# Main_Shield.net
KiCad netlist of a schematic drawn in Altium Designer
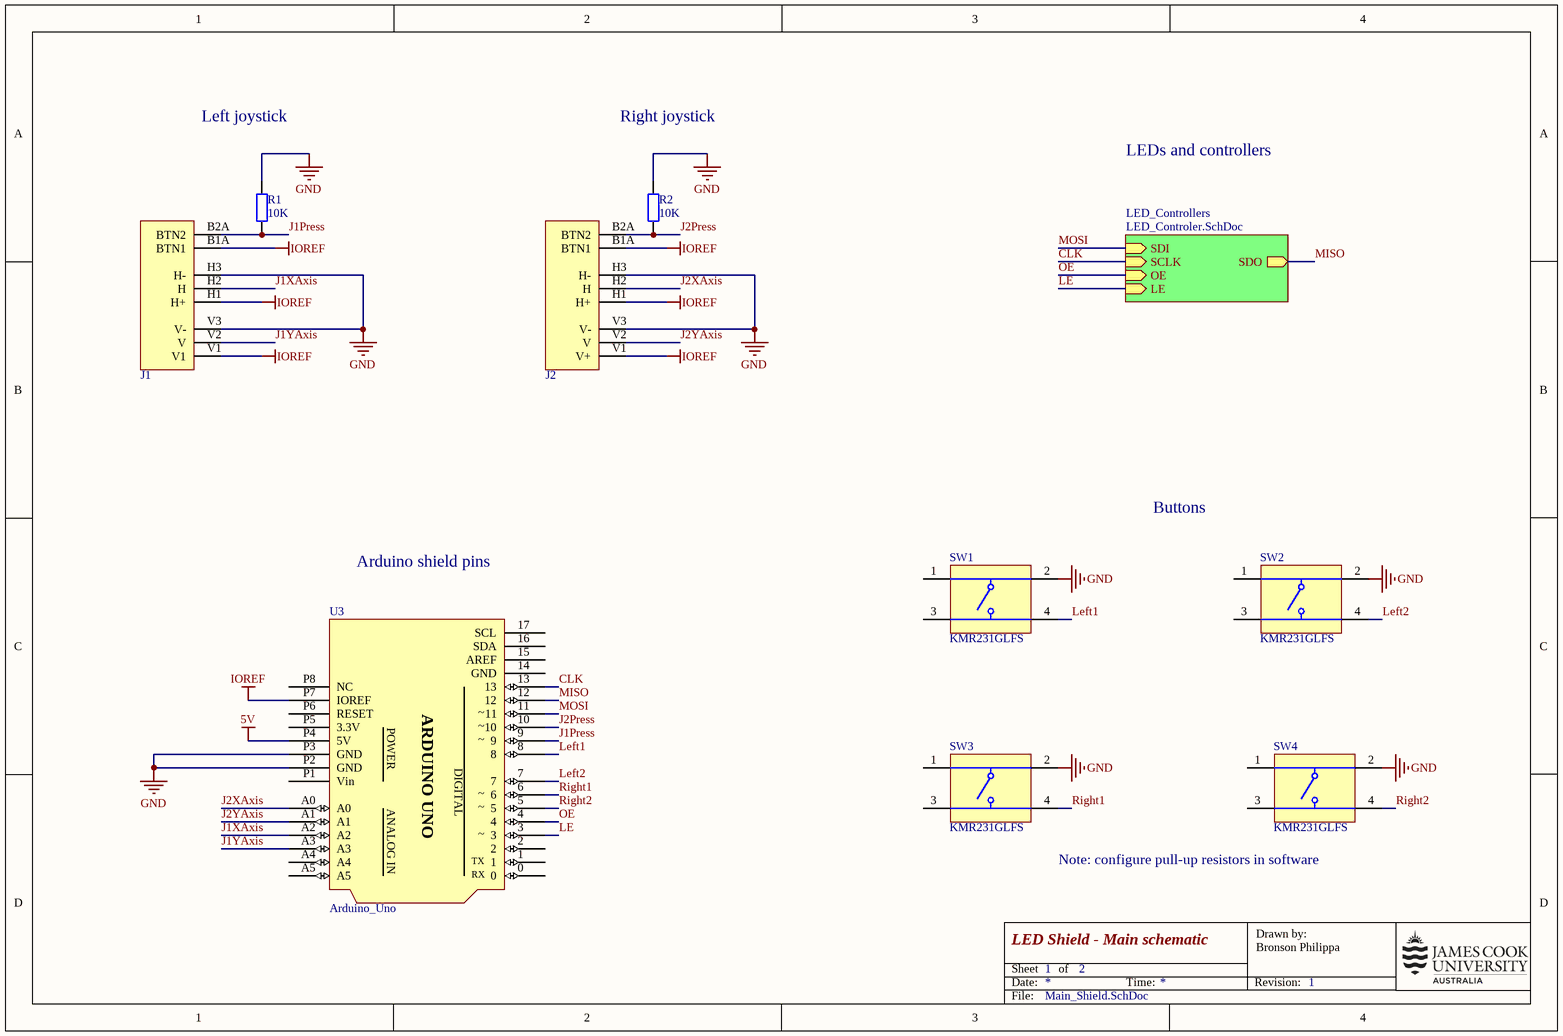
[diagram p0: Main_Shield.SchDoc]

(export (version "E")
  (design (tool "Eeschema 10.0.6"))
  (components
    (comp (ref "J1")
      (value "Joystick")
      (footprint "JOYSTICK")
      (description "Sparkfun Joystick COM-09032")
      (libsource (lib "JCULibrary") (part "Joystick"))
    )
    (comp (ref "J2")
      (value "Joystick")
      (footprint "JOYSTICK")
      (description "Sparkfun Joystick COM-09032")
      (libsource (lib "JCULibrary") (part "Joystick"))
    )
    (comp (ref "R1")
      (value "10K")
      (footprint "AXIAL-0.4")
      (description "Resistor")
      (fields (field (name "Comment") "Resistor Axial-0.4") (field (name "PUBLISHER") "Altium Limited"))
      (libsource (lib "JCULibrary") (part "Resistor Axial-0.4"))
    )
    (comp (ref "R2")
      (value "10K")
      (footprint "AXIAL-0.4")
      (description "Resistor")
      (fields (field (name "Comment") "Resistor Axial-0.4") (field (name "PUBLISHER") "Altium Limited"))
      (libsource (lib "JCULibrary") (part "Resistor Axial-0.4"))
    )
    (comp (ref "SW1")
      (value "KMR231GLFS")
      (footprint "CKCP-KMR231GLFS")
      (description "Switch Tactile, SPST, 50 mA, 32 V, -40 to 85 degC, 4-Pin SMD, RoHS, Tape and Reel")
      (fields (field (name "MANUFACTURER") "C&K Components"))
      (libsource (lib "Altium Content Vault") (part "SW-SPST-4_A"))
    )
    (comp (ref "SW2")
      (value "KMR231GLFS")
      (footprint "CKCP-KMR231GLFS")
      (description "Switch Tactile, SPST, 50 mA, 32 V, -40 to 85 degC, 4-Pin SMD, RoHS, Tape and Reel")
      (fields (field (name "MANUFACTURER") "C&K Components"))
      (libsource (lib "Altium Content Vault") (part "SW-SPST-4_A"))
    )
    (comp (ref "SW3")
      (value "KMR231GLFS")
      (footprint "CKCP-KMR231GLFS")
      (description "Switch Tactile, SPST, 50 mA, 32 V, -40 to 85 degC, 4-Pin SMD, RoHS, Tape and Reel")
      (fields (field (name "MANUFACTURER") "C&K Components"))
      (libsource (lib "Altium Content Vault") (part "SW-SPST-4_A"))
    )
    (comp (ref "SW4")
      (value "KMR231GLFS")
      (footprint "CKCP-KMR231GLFS")
      (description "Switch Tactile, SPST, 50 mA, 32 V, -40 to 85 degC, 4-Pin SMD, RoHS, Tape and Reel")
      (fields (field (name "MANUFACTURER") "C&K Components"))
      (libsource (lib "Altium Content Vault") (part "SW-SPST-4_A"))
    )
    (comp (ref "U3")
      (value "Arduino_Uno")
      (footprint "ArduinoUnoR3")
      (description "Template for building an Arduino shield")
      (libsource (lib "JCULibrary") (part "Arduino_Uno"))
    )
  )
  (nets
    (net (code "1") (name "/CLK") (class "Default")
      (node (ref "U3") (pin "13") (pinfunction "13_13") (pintype "bidirectional"))
    )
    (net (code "2") (name "/J1Press") (class "Default")
      (node (ref "J1") (pin "B2A") (pinfunction "BTN2_B2A") (pintype "passive"))
      (node (ref "R1") (pin "2") (pinfunction "2_2") (pintype "passive"))
      (node (ref "U3") (pin "9") (pinfunction "9_9") (pintype "bidirectional"))
    )
    (net (code "3") (name "/J1XAxis") (class "Default")
      (node (ref "J1") (pin "H2") (pinfunction "H_H2") (pintype "passive"))
      (node (ref "U3") (pin "A2") (pinfunction "A2_A2") (pintype "bidirectional"))
    )
    (net (code "4") (name "/J1YAxis") (class "Default")
      (node (ref "J1") (pin "V2") (pinfunction "V_V2") (pintype "passive"))
      (node (ref "U3") (pin "A3") (pinfunction "A3_A3") (pintype "bidirectional"))
    )
    (net (code "5") (name "/J2Press") (class "Default")
      (node (ref "J2") (pin "B2A") (pinfunction "BTN2_B2A") (pintype "passive"))
      (node (ref "R2") (pin "2") (pinfunction "2_2") (pintype "passive"))
      (node (ref "U3") (pin "10") (pinfunction "10_10") (pintype "bidirectional"))
    )
    (net (code "6") (name "/J2XAxis") (class "Default")
      (node (ref "J2") (pin "H2") (pinfunction "H_H2") (pintype "passive"))
      (node (ref "U3") (pin "A0") (pinfunction "A0_A0") (pintype "bidirectional"))
    )
    (net (code "7") (name "/J2YAxis") (class "Default")
      (node (ref "J2") (pin "V2") (pinfunction "V_V2") (pintype "passive"))
      (node (ref "U3") (pin "A1") (pinfunction "A1_A1") (pintype "bidirectional"))
    )
    (net (code "8") (name "/LE") (class "Default")
      (node (ref "U3") (pin "3") (pinfunction "3_3") (pintype "bidirectional"))
    )
    (net (code "9") (name "/Left1") (class "Default")
      (node (ref "SW1") (pin "4") (pinfunction "4_4") (pintype "passive"))
      (node (ref "U3") (pin "8") (pinfunction "8_8") (pintype "bidirectional"))
    )
    (net (code "10") (name "/Left2") (class "Default")
      (node (ref "SW2") (pin "4") (pinfunction "4_4") (pintype "passive"))
      (node (ref "U3") (pin "7") (pinfunction "7_7") (pintype "bidirectional"))
    )
    (net (code "11") (name "/MISO") (class "Default")
      (node (ref "U3") (pin "12") (pinfunction "12_12") (pintype "bidirectional"))
    )
    (net (code "12") (name "/MOSI") (class "Default")
      (node (ref "U3") (pin "11") (pinfunction "11_11") (pintype "bidirectional"))
    )
    (net (code "13") (name "/OE") (class "Default")
      (node (ref "U3") (pin "4") (pinfunction "4_4") (pintype "bidirectional"))
    )
    (net (code "14") (name "/Right1") (class "Default")
      (node (ref "SW3") (pin "4") (pinfunction "4_4") (pintype "passive"))
      (node (ref "U3") (pin "6") (pinfunction "6_6") (pintype "bidirectional"))
    )
    (net (code "15") (name "/Right2") (class "Default")
      (node (ref "SW4") (pin "4") (pinfunction "4_4") (pintype "passive"))
      (node (ref "U3") (pin "5") (pinfunction "5_5") (pintype "bidirectional"))
    )
    (net (code "16") (name "5V") (class "Default")
      (node (ref "U3") (pin "P4") (pinfunction "5V_P4") (pintype "power_in"))
    )
    (net (code "17") (name "GND") (class "Default")
      (node (ref "J1") (pin "H3") (pinfunction "H-_H3") (pintype "passive"))
      (node (ref "J1") (pin "V3") (pinfunction "V-_V3") (pintype "passive"))
      (node (ref "J2") (pin "H3") (pinfunction "H-_H3") (pintype "passive"))
      (node (ref "J2") (pin "V3") (pinfunction "V-_V3") (pintype "passive"))
      (node (ref "R1") (pin "1") (pinfunction "1_1") (pintype "passive"))
      (node (ref "R2") (pin "1") (pinfunction "1_1") (pintype "passive"))
      (node (ref "SW1") (pin "2") (pinfunction "2_2") (pintype "passive"))
      (node (ref "SW2") (pin "2") (pinfunction "2_2") (pintype "passive"))
      (node (ref "SW3") (pin "2") (pinfunction "2_2") (pintype "passive"))
      (node (ref "SW4") (pin "2") (pinfunction "2_2") (pintype "passive"))
      (node (ref "U3") (pin "P2") (pinfunction "GND_P2") (pintype "power_in"))
      (node (ref "U3") (pin "P3") (pinfunction "GND_P3") (pintype "power_in"))
    )
    (net (code "18") (name "IOREF") (class "Default")
      (node (ref "J1") (pin "B1A") (pinfunction "BTN1_B1A") (pintype "passive"))
      (node (ref "J1") (pin "H1") (pinfunction "H+_H1") (pintype "passive"))
      (node (ref "J1") (pin "V1") (pinfunction "V1_V1") (pintype "passive"))
      (node (ref "J2") (pin "B1A") (pinfunction "BTN1_B1A") (pintype "passive"))
      (node (ref "J2") (pin "H1") (pinfunction "H+_H1") (pintype "passive"))
      (node (ref "J2") (pin "V1") (pinfunction "V1_V1") (pintype "passive"))
      (node (ref "U3") (pin "P7") (pinfunction "IOREF_P7") (pintype "power_in"))
    )
    (net (code "19") (name "unconnected-(SW1-Pad1)") (class "Default")
      (node (ref "SW1") (pin "1") (pinfunction "1_1") (pintype "passive"))
    )
    (net (code "20") (name "unconnected-(SW1-Pad3)") (class "Default")
      (node (ref "SW1") (pin "3") (pinfunction "3_3") (pintype "passive"))
    )
    (net (code "21") (name "unconnected-(SW2-Pad1)") (class "Default")
      (node (ref "SW2") (pin "1") (pinfunction "1_1") (pintype "passive"))
    )
    (net (code "22") (name "unconnected-(SW2-Pad3)") (class "Default")
      (node (ref "SW2") (pin "3") (pinfunction "3_3") (pintype "passive"))
    )
    (net (code "23") (name "unconnected-(SW3-Pad1)") (class "Default")
      (node (ref "SW3") (pin "1") (pinfunction "1_1") (pintype "passive"))
    )
    (net (code "24") (name "unconnected-(SW3-Pad3)") (class "Default")
      (node (ref "SW3") (pin "3") (pinfunction "3_3") (pintype "passive"))
    )
    (net (code "25") (name "unconnected-(SW4-Pad1)") (class "Default")
      (node (ref "SW4") (pin "1") (pinfunction "1_1") (pintype "passive"))
    )
    (net (code "26") (name "unconnected-(SW4-Pad3)") (class "Default")
      (node (ref "SW4") (pin "3") (pinfunction "3_3") (pintype "passive"))
    )
    (net (code "27") (name "unconnected-(U3-3.3V-PadP5)") (class "Default")
      (node (ref "U3") (pin "P5") (pinfunction "3.3V_P5") (pintype "power_in"))
    )
    (net (code "28") (name "unconnected-(U3-AREF-Pad15)") (class "Default")
      (node (ref "U3") (pin "15") (pinfunction "AREF_15") (pintype "power_in"))
    )
    (net (code "29") (name "unconnected-(U3-GND-Pad14)") (class "Default")
      (node (ref "U3") (pin "14") (pinfunction "GND_14") (pintype "power_in"))
    )
    (net (code "30") (name "unconnected-(U3-NC-PadP8)") (class "Default")
      (node (ref "U3") (pin "P8") (pinfunction "NC_P8") (pintype "passive"))
    )
    (net (code "31") (name "unconnected-(U3-Pad0)") (class "Default")
      (node (ref "U3") (pin "0") (pinfunction "0_0") (pintype "bidirectional"))
    )
    (net (code "32") (name "unconnected-(U3-Pad1)") (class "Default")
      (node (ref "U3") (pin "1") (pinfunction "1_1") (pintype "bidirectional"))
    )
    (net (code "33") (name "unconnected-(U3-Pad2)") (class "Default")
      (node (ref "U3") (pin "2") (pinfunction "2_2") (pintype "bidirectional"))
    )
    (net (code "34") (name "unconnected-(U3-PadA4)") (class "Default")
      (node (ref "U3") (pin "A4") (pinfunction "A4_A4") (pintype "bidirectional"))
    )
    (net (code "35") (name "unconnected-(U3-PadA5)") (class "Default")
      (node (ref "U3") (pin "A5") (pinfunction "A5_A5") (pintype "bidirectional"))
    )
    (net (code "36") (name "unconnected-(U3-RESET-PadP6)") (class "Default")
      (node (ref "U3") (pin "P6") (pinfunction "RESET_P6") (pintype "passive"))
    )
    (net (code "37") (name "unconnected-(U3-SCL-Pad17)") (class "Default")
      (node (ref "U3") (pin "17") (pinfunction "SCL_17") (pintype "power_in"))
    )
    (net (code "38") (name "unconnected-(U3-SDA-Pad16)") (class "Default")
      (node (ref "U3") (pin "16") (pinfunction "SDA_16") (pintype "power_in"))
    )
    (net (code "39") (name "unconnected-(U3-Vin-PadP1)") (class "Default")
      (node (ref "U3") (pin "P1") (pinfunction "Vin_P1") (pintype "passive"))
    )
  )
)
